# LDAQ-MOD-ENC4.net
KiCad netlist of a schematic drawn in EAGLE
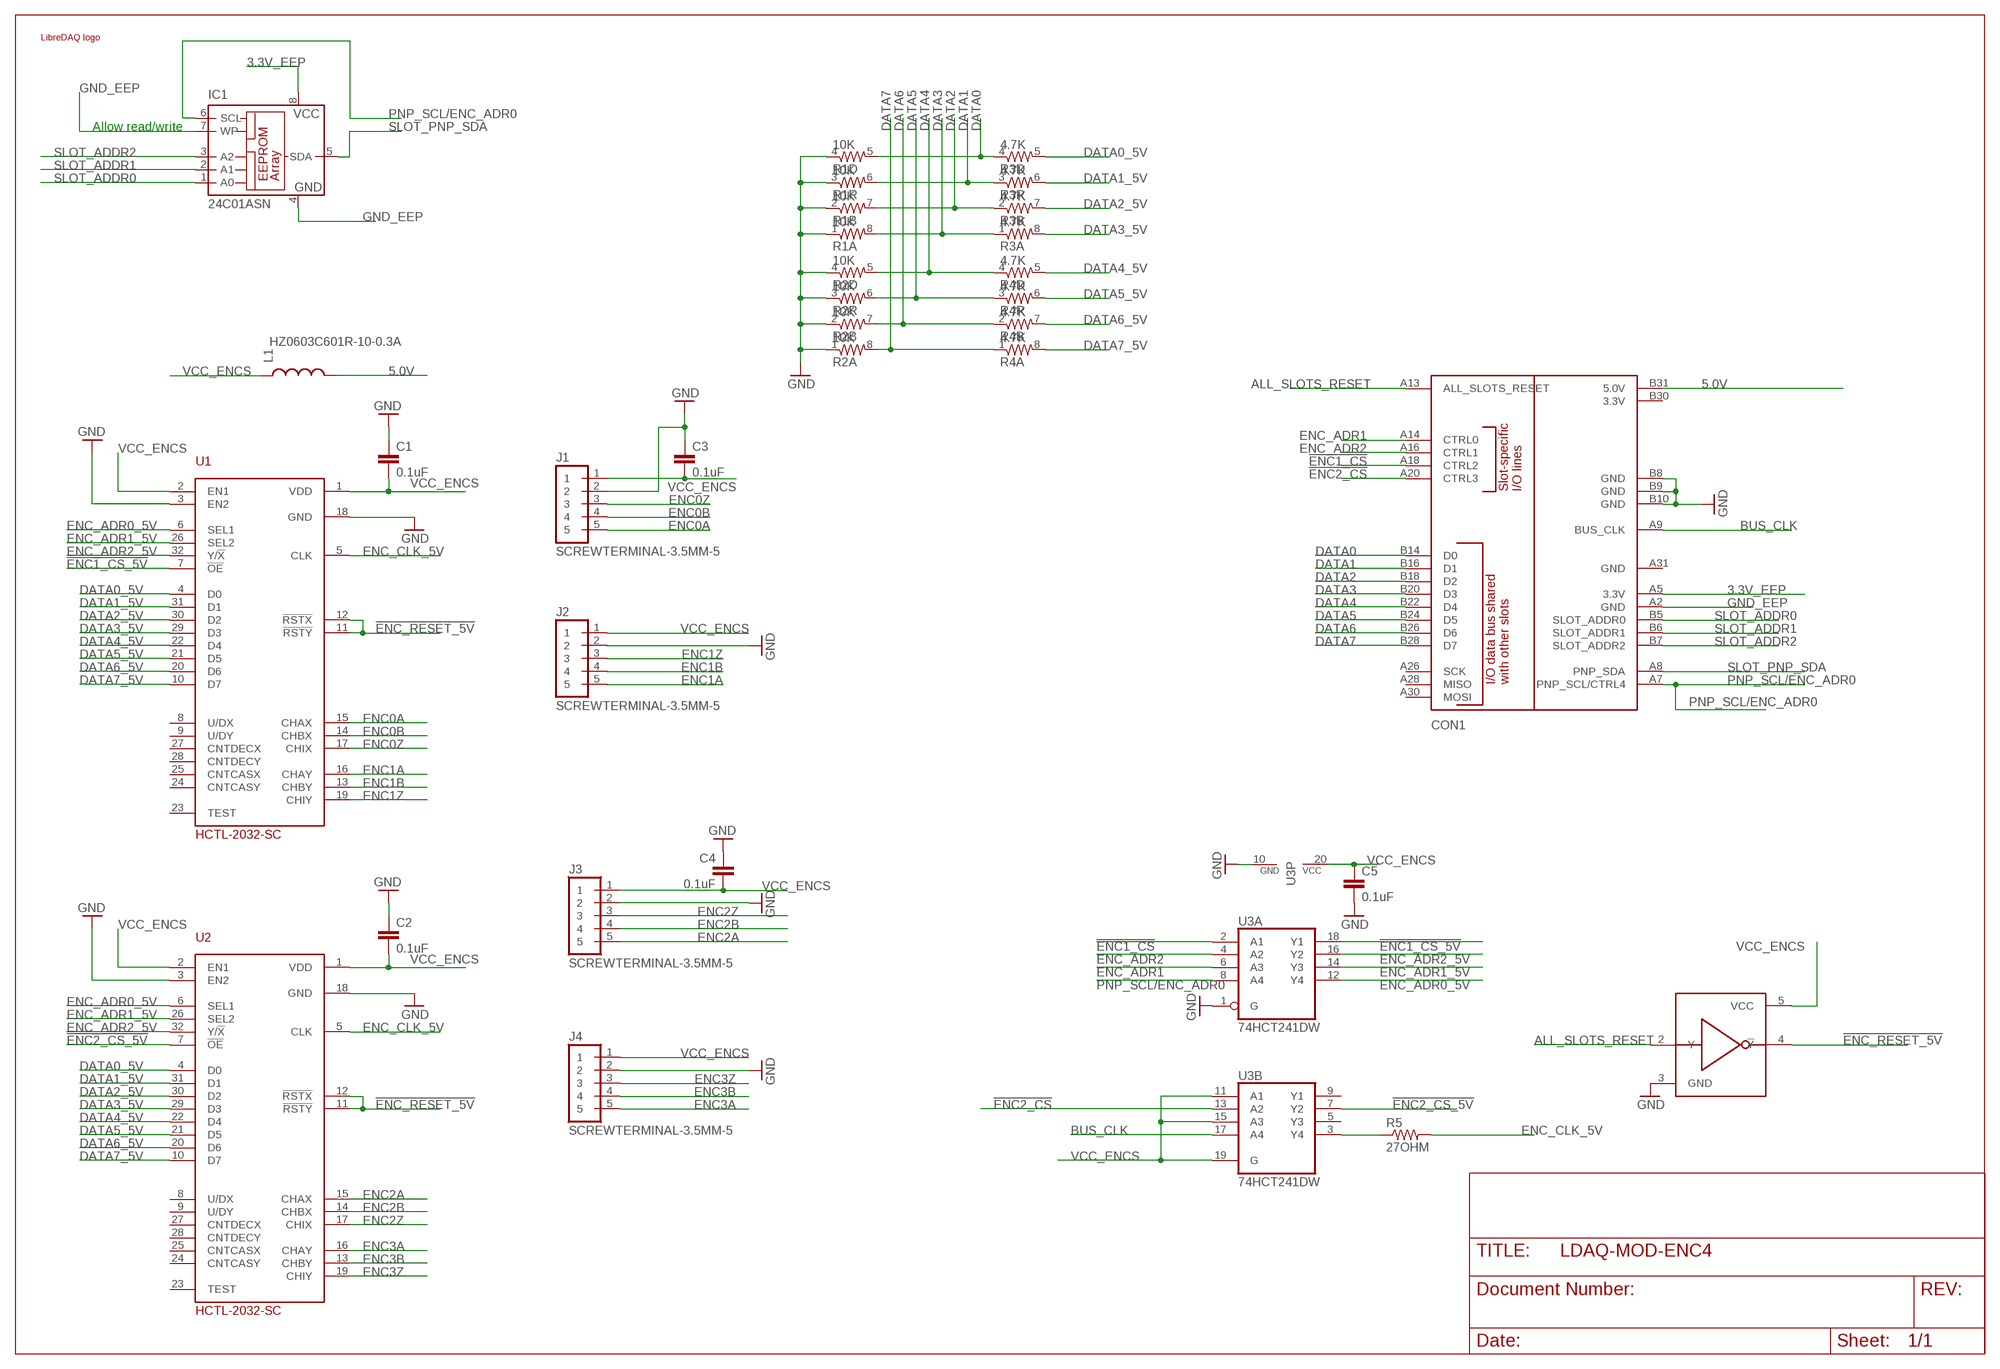
[diagram p0: schematic, sheet 1]

(export (version "E")
  (design (tool "Eeschema 10.0.6"))
  (components
    (comp (ref "C1")
      (value "0.1uF")
      (footprint "eagle-import:0603-CAP")
      (libsource (lib "eagle-import") (part "0.1UF-25V(+80/-20%)(0603)"))
    )
    (comp (ref "C2")
      (value "0.1uF")
      (footprint "eagle-import:0603-CAP")
      (libsource (lib "eagle-import") (part "0.1UF-25V(+80/-20%)(0603)"))
    )
    (comp (ref "C3")
      (value "0.1uF")
      (footprint "eagle-import:0603-CAP")
      (libsource (lib "eagle-import") (part "0.1UF-25V(+80/-20%)(0603)"))
    )
    (comp (ref "C4")
      (value "0.1uF")
      (footprint "eagle-import:0603-CAP")
      (libsource (lib "eagle-import") (part "0.1UF-25V(+80/-20%)(0603)"))
    )
    (comp (ref "C5")
      (value "0.1uF")
      (footprint "eagle-import:0603-CAP")
      (libsource (lib "eagle-import") (part "0.1UF-25V(+80/-20%)(0603)"))
    )
    (comp (ref "CON1")
      (value "BOARD")
      (footprint "eagle-import:PCI-E_64_EDGE_70X60_PADS-ONLY")
      (libsource (lib "eagle-import") (part "LIBREDAQ_DAUGHTER_BOARDPCI-64-SIZE1-PADS"))
    )
    (comp (ref "IC1")
      (value "24C01ASN")
      (footprint "eagle-import:SO-08")
      (fields (field (name "MPN") "AT24C01BN-SH-B"))
      (libsource (lib "eagle-import") (part "24CSN01A"))
    )
    (comp (ref "J1")
      (value "SCREWTERMINAL-3.5MM-5")
      (footprint "eagle-import:SCREWTERMINAL-3.5MM-5")
      (libsource (lib "eagle-import") (part "SCREWTERMINAL-3.5MM-5"))
    )
    (comp (ref "J2")
      (value "SCREWTERMINAL-3.5MM-5")
      (footprint "eagle-import:SCREWTERMINAL-3.5MM-5")
      (libsource (lib "eagle-import") (part "SCREWTERMINAL-3.5MM-5"))
    )
    (comp (ref "J3")
      (value "SCREWTERMINAL-3.5MM-5")
      (footprint "eagle-import:SCREWTERMINAL-3.5MM-5")
      (libsource (lib "eagle-import") (part "SCREWTERMINAL-3.5MM-5"))
    )
    (comp (ref "J4")
      (value "SCREWTERMINAL-3.5MM-5")
      (footprint "eagle-import:SCREWTERMINAL-3.5MM-5")
      (libsource (lib "eagle-import") (part "SCREWTERMINAL-3.5MM-5"))
    )
    (comp (ref "L1")
      (value "HZ0603C601R-10-0.3A")
      (footprint "eagle-import:0603")
      (libsource (lib "eagle-import") (part "INDUCTOR0603"))
    )
    (comp (ref "LOGO1")
      (value "LIBREDAQ_LOGO_MINILOGO_GENERIC")
      (footprint "eagle-import:LIBREDAQ_LOGO")
      (libsource (lib "eagle-import") (part "LIBREDAQ_LOGO_MINILOGO_GENERIC"))
    )
    (comp (ref "R1")
      (value "10K")
      (footprint "eagle-import:0603-ARV")
      (libsource (lib "eagle-import") (part "RESISTOR-ARRAY0603-ARV"))
    )
    (comp (ref "R2")
      (value "10K")
      (footprint "eagle-import:0603-ARV")
      (libsource (lib "eagle-import") (part "RESISTOR-ARRAY0603-ARV"))
    )
    (comp (ref "R3")
      (value "4.7K")
      (footprint "eagle-import:0603-ARV")
      (libsource (lib "eagle-import") (part "RESISTOR-ARRAY0603-ARV"))
    )
    (comp (ref "R4")
      (value "4.7K")
      (footprint "eagle-import:0603-ARV")
      (libsource (lib "eagle-import") (part "RESISTOR-ARRAY0603-ARV"))
    )
    (comp (ref "R5")
      (value "27OHM")
      (footprint "eagle-import:0603")
      (libsource (lib "eagle-import") (part "33OHM1/10W1%(0603)"))
    )
    (comp (ref "U1")
      (value "HCTL-2032-SC")
      (footprint "eagle-import:SOIC32")
      (libsource (lib "eagle-import") (part "HCTL-2032-SC"))
    )
    (comp (ref "U2")
      (value "HCTL-2032-SC")
      (footprint "eagle-import:SOIC32")
      (libsource (lib "eagle-import") (part "HCTL-2032-SC"))
    )
    (comp (ref "U3")
      (value "74HCT241DW")
      (footprint "eagle-import:SO20W")
      (libsource (lib "eagle-import") (part "74241DWHCT"))
    )
    (comp (ref "U4")
      (value "74AHCT1G04")
      (footprint "eagle-import:SOT353-SC70-5")
      (libsource (lib "eagle-import") (part "74AHCT1G04"))
    )
  )
  (nets
    (net (code "1") (name "/3.3V_EEP") (class "Default")
      (node (ref "CON1") (pin "A5") (pinfunction "3.3V_A5") (pintype "bidirectional"))
      (node (ref "IC1") (pin "8") (pinfunction "VCC_8") (pintype "power_in"))
    )
    (net (code "2") (name "/5.0V") (class "Default")
      (node (ref "CON1") (pin "B31") (pinfunction "5.0V_B31") (pintype "bidirectional"))
      (node (ref "L1") (pin "2") (pinfunction "2_2") (pintype "passive"))
    )
    (net (code "3") (name "/ALL_SLOTS_RESET") (class "Default")
      (node (ref "CON1") (pin "A13") (pinfunction "ALL_SLOTS_RESET_A13") (pintype "bidirectional"))
      (node (ref "U4") (pin "2") (pinfunction "Y_2") (pintype "bidirectional"))
    )
    (net (code "4") (name "/BUS_CLK") (class "Default")
      (node (ref "CON1") (pin "A9") (pinfunction "BUS_CLK_A9") (pintype "bidirectional"))
      (node (ref "U3") (pin "17") (pinfunction "A4_17") (pintype "input"))
    )
    (net (code "5") (name "/DATA0") (class "Default")
      (node (ref "CON1") (pin "B14") (pinfunction "D0_B14") (pintype "bidirectional"))
      (node (ref "R1") (pin "5") (pinfunction "2_5") (pintype "passive"))
      (node (ref "R3") (pin "4") (pinfunction "1_4") (pintype "passive"))
    )
    (net (code "6") (name "/DATA0_5V") (class "Default")
      (node (ref "R3") (pin "5") (pinfunction "2_5") (pintype "passive"))
      (node (ref "U1") (pin "4") (pinfunction "D0_4") (pintype "bidirectional"))
      (node (ref "U2") (pin "4") (pinfunction "D0_4") (pintype "bidirectional"))
    )
    (net (code "7") (name "/DATA1") (class "Default")
      (node (ref "CON1") (pin "B16") (pinfunction "D1_B16") (pintype "bidirectional"))
      (node (ref "R1") (pin "6") (pinfunction "2_6") (pintype "passive"))
      (node (ref "R3") (pin "3") (pinfunction "1_3") (pintype "passive"))
    )
    (net (code "8") (name "/DATA1_5V") (class "Default")
      (node (ref "R3") (pin "6") (pinfunction "2_6") (pintype "passive"))
      (node (ref "U1") (pin "31") (pinfunction "D1_31") (pintype "bidirectional"))
      (node (ref "U2") (pin "31") (pinfunction "D1_31") (pintype "bidirectional"))
    )
    (net (code "9") (name "/DATA2") (class "Default")
      (node (ref "CON1") (pin "B18") (pinfunction "D2_B18") (pintype "bidirectional"))
      (node (ref "R1") (pin "7") (pinfunction "2_7") (pintype "passive"))
      (node (ref "R3") (pin "2") (pinfunction "1_2") (pintype "passive"))
    )
    (net (code "10") (name "/DATA2_5V") (class "Default")
      (node (ref "R3") (pin "7") (pinfunction "2_7") (pintype "passive"))
      (node (ref "U1") (pin "30") (pinfunction "D2_30") (pintype "bidirectional"))
      (node (ref "U2") (pin "30") (pinfunction "D2_30") (pintype "bidirectional"))
    )
    (net (code "11") (name "/DATA3") (class "Default")
      (node (ref "CON1") (pin "B20") (pinfunction "D3_B20") (pintype "bidirectional"))
      (node (ref "R1") (pin "8") (pinfunction "2_8") (pintype "passive"))
      (node (ref "R3") (pin "1") (pinfunction "1_1") (pintype "passive"))
    )
    (net (code "12") (name "/DATA3_5V") (class "Default")
      (node (ref "R3") (pin "8") (pinfunction "2_8") (pintype "passive"))
      (node (ref "U1") (pin "29") (pinfunction "D3_29") (pintype "bidirectional"))
      (node (ref "U2") (pin "29") (pinfunction "D3_29") (pintype "bidirectional"))
    )
    (net (code "13") (name "/DATA4") (class "Default")
      (node (ref "CON1") (pin "B22") (pinfunction "D4_B22") (pintype "bidirectional"))
      (node (ref "R2") (pin "5") (pinfunction "2_5") (pintype "passive"))
      (node (ref "R4") (pin "4") (pinfunction "1_4") (pintype "passive"))
    )
    (net (code "14") (name "/DATA4_5V") (class "Default")
      (node (ref "R4") (pin "5") (pinfunction "2_5") (pintype "passive"))
      (node (ref "U1") (pin "22") (pinfunction "D4_22") (pintype "bidirectional"))
      (node (ref "U2") (pin "22") (pinfunction "D4_22") (pintype "bidirectional"))
    )
    (net (code "15") (name "/DATA5") (class "Default")
      (node (ref "CON1") (pin "B24") (pinfunction "D5_B24") (pintype "bidirectional"))
      (node (ref "R2") (pin "6") (pinfunction "2_6") (pintype "passive"))
      (node (ref "R4") (pin "3") (pinfunction "1_3") (pintype "passive"))
    )
    (net (code "16") (name "/DATA5_5V") (class "Default")
      (node (ref "R4") (pin "6") (pinfunction "2_6") (pintype "passive"))
      (node (ref "U1") (pin "21") (pinfunction "D5_21") (pintype "bidirectional"))
      (node (ref "U2") (pin "21") (pinfunction "D5_21") (pintype "bidirectional"))
    )
    (net (code "17") (name "/DATA6") (class "Default")
      (node (ref "CON1") (pin "B26") (pinfunction "D6_B26") (pintype "bidirectional"))
      (node (ref "R2") (pin "7") (pinfunction "2_7") (pintype "passive"))
      (node (ref "R4") (pin "2") (pinfunction "1_2") (pintype "passive"))
    )
    (net (code "18") (name "/DATA6_5V") (class "Default")
      (node (ref "R4") (pin "7") (pinfunction "2_7") (pintype "passive"))
      (node (ref "U1") (pin "20") (pinfunction "D6_20") (pintype "bidirectional"))
      (node (ref "U2") (pin "20") (pinfunction "D6_20") (pintype "bidirectional"))
    )
    (net (code "19") (name "/DATA7") (class "Default")
      (node (ref "CON1") (pin "B28") (pinfunction "D7_B28") (pintype "bidirectional"))
      (node (ref "R2") (pin "8") (pinfunction "2_8") (pintype "passive"))
      (node (ref "R4") (pin "1") (pinfunction "1_1") (pintype "passive"))
    )
    (net (code "20") (name "/DATA7_5V") (class "Default")
      (node (ref "R4") (pin "8") (pinfunction "2_8") (pintype "passive"))
      (node (ref "U1") (pin "10") (pinfunction "D7_10") (pintype "bidirectional"))
      (node (ref "U2") (pin "10") (pinfunction "D7_10") (pintype "bidirectional"))
    )
    (net (code "21") (name "/ENC0A") (class "Default")
      (node (ref "J1") (pin "5") (pinfunction "5_5") (pintype "bidirectional"))
      (node (ref "U1") (pin "15") (pinfunction "CHAX_15") (pintype "bidirectional"))
    )
    (net (code "22") (name "/ENC0B") (class "Default")
      (node (ref "J1") (pin "4") (pinfunction "4_4") (pintype "bidirectional"))
      (node (ref "U1") (pin "14") (pinfunction "CHBX_14") (pintype "bidirectional"))
    )
    (net (code "23") (name "/ENC0Z") (class "Default")
      (node (ref "J1") (pin "3") (pinfunction "3_3") (pintype "bidirectional"))
      (node (ref "U1") (pin "17") (pinfunction "CHIX_17") (pintype "bidirectional"))
    )
    (net (code "24") (name "/ENC1A") (class "Default")
      (node (ref "J2") (pin "5") (pinfunction "5_5") (pintype "bidirectional"))
      (node (ref "U1") (pin "16") (pinfunction "CHAY_16") (pintype "bidirectional"))
    )
    (net (code "25") (name "/ENC1B") (class "Default")
      (node (ref "J2") (pin "4") (pinfunction "4_4") (pintype "bidirectional"))
      (node (ref "U1") (pin "13") (pinfunction "CHBY_13") (pintype "bidirectional"))
    )
    (net (code "26") (name "/ENC1Z") (class "Default")
      (node (ref "J2") (pin "3") (pinfunction "3_3") (pintype "bidirectional"))
      (node (ref "U1") (pin "19") (pinfunction "CHIY_19") (pintype "bidirectional"))
    )
    (net (code "27") (name "/ENC2A") (class "Default")
      (node (ref "J3") (pin "5") (pinfunction "5_5") (pintype "bidirectional"))
      (node (ref "U2") (pin "15") (pinfunction "CHAX_15") (pintype "bidirectional"))
    )
    (net (code "28") (name "/ENC2B") (class "Default")
      (node (ref "J3") (pin "4") (pinfunction "4_4") (pintype "bidirectional"))
      (node (ref "U2") (pin "14") (pinfunction "CHBX_14") (pintype "bidirectional"))
    )
    (net (code "29") (name "/ENC2Z") (class "Default")
      (node (ref "J3") (pin "3") (pinfunction "3_3") (pintype "bidirectional"))
      (node (ref "U2") (pin "17") (pinfunction "CHIX_17") (pintype "bidirectional"))
    )
    (net (code "30") (name "/ENC3A") (class "Default")
      (node (ref "J4") (pin "5") (pinfunction "5_5") (pintype "bidirectional"))
      (node (ref "U2") (pin "16") (pinfunction "CHAY_16") (pintype "bidirectional"))
    )
    (net (code "31") (name "/ENC3B") (class "Default")
      (node (ref "J4") (pin "4") (pinfunction "4_4") (pintype "bidirectional"))
      (node (ref "U2") (pin "13") (pinfunction "CHBY_13") (pintype "bidirectional"))
    )
    (net (code "32") (name "/ENC3Z") (class "Default")
      (node (ref "J4") (pin "3") (pinfunction "3_3") (pintype "bidirectional"))
      (node (ref "U2") (pin "19") (pinfunction "CHIY_19") (pintype "bidirectional"))
    )
    (net (code "33") (name "/ENC_ADR0_5V") (class "Default")
      (node (ref "U1") (pin "6") (pinfunction "SEL1_6") (pintype "bidirectional"))
      (node (ref "U2") (pin "6") (pinfunction "SEL1_6") (pintype "bidirectional"))
      (node (ref "U3") (pin "12") (pinfunction "Y4_12") (pintype "tri_state"))
    )
    (net (code "34") (name "/ENC_ADR1") (class "Default")
      (node (ref "CON1") (pin "A14") (pinfunction "CTRL0_A14") (pintype "bidirectional"))
      (node (ref "U3") (pin "6") (pinfunction "A3_6") (pintype "input"))
    )
    (net (code "35") (name "/ENC_ADR1_5V") (class "Default")
      (node (ref "U1") (pin "26") (pinfunction "SEL2_26") (pintype "bidirectional"))
      (node (ref "U2") (pin "26") (pinfunction "SEL2_26") (pintype "bidirectional"))
      (node (ref "U3") (pin "14") (pinfunction "Y3_14") (pintype "tri_state"))
    )
    (net (code "36") (name "/ENC_ADR2") (class "Default")
      (node (ref "CON1") (pin "A16") (pinfunction "CTRL1_A16") (pintype "bidirectional"))
      (node (ref "U3") (pin "4") (pinfunction "A2_4") (pintype "input"))
    )
    (net (code "37") (name "/ENC_ADR2_5V") (class "Default")
      (node (ref "U1") (pin "32") (pinfunction "Y/~{X}_32") (pintype "bidirectional"))
      (node (ref "U2") (pin "32") (pinfunction "Y/~{X}_32") (pintype "bidirectional"))
      (node (ref "U3") (pin "16") (pinfunction "Y2_16") (pintype "tri_state"))
    )
    (net (code "38") (name "/ENC_CLK_5V") (class "Default")
      (node (ref "R5") (pin "2") (pinfunction "2_2") (pintype "passive"))
      (node (ref "U1") (pin "5") (pinfunction "CLK_5") (pintype "bidirectional"))
      (node (ref "U2") (pin "5") (pinfunction "CLK_5") (pintype "bidirectional"))
    )
    (net (code "39") (name "/GND_EEP") (class "Default")
      (node (ref "CON1") (pin "A2") (pinfunction "GND_A2") (pintype "bidirectional"))
      (node (ref "IC1") (pin "4") (pinfunction "GND_4") (pintype "power_in"))
      (node (ref "IC1") (pin "7") (pinfunction "WP_7") (pintype "input"))
    )
    (net (code "40") (name "/PNP_SCL{slash}ENC_ADR0") (class "Default")
      (node (ref "CON1") (pin "A7") (pinfunction "PNP_SCL/CTRL4_A7") (pintype "bidirectional"))
      (node (ref "IC1") (pin "6") (pinfunction "SCL_6") (pintype "input"))
      (node (ref "U3") (pin "8") (pinfunction "A4_8") (pintype "input"))
    )
    (net (code "41") (name "/SLOT_ADDR0") (class "Default")
      (node (ref "CON1") (pin "B5") (pinfunction "SLOT_ADDR0_B5") (pintype "bidirectional"))
      (node (ref "IC1") (pin "1") (pinfunction "A0_1") (pintype "input"))
    )
    (net (code "42") (name "/SLOT_ADDR1") (class "Default")
      (node (ref "CON1") (pin "B6") (pinfunction "SLOT_ADDR1_B6") (pintype "bidirectional"))
      (node (ref "IC1") (pin "2") (pinfunction "A1_2") (pintype "input"))
    )
    (net (code "43") (name "/SLOT_ADDR2") (class "Default")
      (node (ref "CON1") (pin "B7") (pinfunction "SLOT_ADDR2_B7") (pintype "bidirectional"))
      (node (ref "IC1") (pin "3") (pinfunction "A2_3") (pintype "input"))
    )
    (net (code "44") (name "/SLOT_PNP_SDA") (class "Default")
      (node (ref "CON1") (pin "A8") (pinfunction "PNP_SDA_A8") (pintype "bidirectional"))
      (node (ref "IC1") (pin "5") (pinfunction "SDA_5") (pintype "bidirectional"))
    )
    (net (code "45") (name "/VCC_ENCS") (class "Default")
      (node (ref "C1") (pin "2") (pinfunction "2_2") (pintype "passive"))
      (node (ref "C2") (pin "2") (pinfunction "2_2") (pintype "passive"))
      (node (ref "C3") (pin "2") (pinfunction "2_2") (pintype "passive"))
      (node (ref "C4") (pin "2") (pinfunction "2_2") (pintype "passive"))
      (node (ref "C5") (pin "1") (pinfunction "1_1") (pintype "passive"))
      (node (ref "J1") (pin "1") (pinfunction "1_1") (pintype "bidirectional"))
      (node (ref "J2") (pin "1") (pinfunction "1_1") (pintype "bidirectional"))
      (node (ref "J3") (pin "1") (pinfunction "1_1") (pintype "bidirectional"))
      (node (ref "J4") (pin "1") (pinfunction "1_1") (pintype "bidirectional"))
      (node (ref "L1") (pin "1") (pinfunction "1_1") (pintype "passive"))
      (node (ref "U1") (pin "1") (pinfunction "VDD_1") (pintype "bidirectional"))
      (node (ref "U1") (pin "2") (pinfunction "EN1_2") (pintype "bidirectional"))
      (node (ref "U2") (pin "1") (pinfunction "VDD_1") (pintype "bidirectional"))
      (node (ref "U2") (pin "2") (pinfunction "EN1_2") (pintype "bidirectional"))
      (node (ref "U3") (pin "11") (pinfunction "A1_11") (pintype "input"))
      (node (ref "U3") (pin "15") (pinfunction "A3_15") (pintype "input"))
      (node (ref "U3") (pin "19") (pinfunction "G_19") (pintype "input"))
      (node (ref "U3") (pin "20") (pinfunction "VCC_20") (pintype "power_in"))
      (node (ref "U4") (pin "5") (pinfunction "VCC_5") (pintype "bidirectional"))
    )
    (net (code "46") (name "/~{ENC1_CS_5V}") (class "Default")
      (node (ref "U1") (pin "7") (pinfunction "~{OE}_7") (pintype "bidirectional"))
      (node (ref "U3") (pin "18") (pinfunction "Y1_18") (pintype "tri_state"))
    )
    (net (code "47") (name "/~{ENC1_CS}") (class "Default")
      (node (ref "CON1") (pin "A18") (pinfunction "CTRL2_A18") (pintype "bidirectional"))
      (node (ref "U3") (pin "2") (pinfunction "A1_2") (pintype "input"))
    )
    (net (code "48") (name "/~{ENC2_CS_5V}") (class "Default")
      (node (ref "U2") (pin "7") (pinfunction "~{OE}_7") (pintype "bidirectional"))
      (node (ref "U3") (pin "7") (pinfunction "Y2_7") (pintype "tri_state"))
    )
    (net (code "49") (name "/~{ENC2_CS}") (class "Default")
      (node (ref "CON1") (pin "A20") (pinfunction "CTRL3_A20") (pintype "bidirectional"))
      (node (ref "U3") (pin "13") (pinfunction "A2_13") (pintype "input"))
    )
    (net (code "50") (name "/~{ENC_RESET_5V}") (class "Default")
      (node (ref "U1") (pin "11") (pinfunction "~{RSTY}_11") (pintype "bidirectional"))
      (node (ref "U1") (pin "12") (pinfunction "~{RSTX}_12") (pintype "bidirectional"))
      (node (ref "U2") (pin "11") (pinfunction "~{RSTY}_11") (pintype "bidirectional"))
      (node (ref "U2") (pin "12") (pinfunction "~{RSTX}_12") (pintype "bidirectional"))
      (node (ref "U4") (pin "4") (pinfunction "~{Y}_4") (pintype "bidirectional"))
    )
    (net (code "51") (name "GND") (class "Default")
      (node (ref "C1") (pin "1") (pinfunction "1_1") (pintype "passive"))
      (node (ref "C2") (pin "1") (pinfunction "1_1") (pintype "passive"))
      (node (ref "C3") (pin "1") (pinfunction "1_1") (pintype "passive"))
      (node (ref "C4") (pin "1") (pinfunction "1_1") (pintype "passive"))
      (node (ref "C5") (pin "2") (pinfunction "2_2") (pintype "passive"))
      (node (ref "CON1") (pin "B10") (pinfunction "GND_B10") (pintype "bidirectional"))
      (node (ref "CON1") (pin "B8") (pinfunction "GND_B8") (pintype "bidirectional"))
      (node (ref "CON1") (pin "B9") (pinfunction "GND_B9") (pintype "bidirectional"))
      (node (ref "J1") (pin "2") (pinfunction "2_2") (pintype "bidirectional"))
      (node (ref "J2") (pin "2") (pinfunction "2_2") (pintype "bidirectional"))
      (node (ref "J3") (pin "2") (pinfunction "2_2") (pintype "bidirectional"))
      (node (ref "J4") (pin "2") (pinfunction "2_2") (pintype "bidirectional"))
      (node (ref "R1") (pin "1") (pinfunction "1_1") (pintype "passive"))
      (node (ref "R1") (pin "2") (pinfunction "1_2") (pintype "passive"))
      (node (ref "R1") (pin "3") (pinfunction "1_3") (pintype "passive"))
      (node (ref "R1") (pin "4") (pinfunction "1_4") (pintype "passive"))
      (node (ref "R2") (pin "1") (pinfunction "1_1") (pintype "passive"))
      (node (ref "R2") (pin "2") (pinfunction "1_2") (pintype "passive"))
      (node (ref "R2") (pin "3") (pinfunction "1_3") (pintype "passive"))
      (node (ref "R2") (pin "4") (pinfunction "1_4") (pintype "passive"))
      (node (ref "U1") (pin "18") (pinfunction "GND_18") (pintype "bidirectional"))
      (node (ref "U1") (pin "3") (pinfunction "EN2_3") (pintype "bidirectional"))
      (node (ref "U2") (pin "18") (pinfunction "GND_18") (pintype "bidirectional"))
      (node (ref "U2") (pin "3") (pinfunction "EN2_3") (pintype "bidirectional"))
      (node (ref "U3") (pin "1") (pinfunction "G_1") (pintype "input"))
      (node (ref "U3") (pin "10") (pinfunction "GND_10") (pintype "power_in"))
      (node (ref "U4") (pin "3") (pinfunction "GND_3") (pintype "bidirectional"))
    )
    (net (code "52") (name "Net-(U3B-Y4)") (class "Default")
      (node (ref "R5") (pin "1") (pinfunction "1_1") (pintype "passive"))
      (node (ref "U3") (pin "3") (pinfunction "Y4_3") (pintype "tri_state"))
    )
    (net (code "53") (name "unconnected-(CON1-3.3V-PadB30)") (class "Default")
      (node (ref "CON1") (pin "B30") (pinfunction "3.3V_B30") (pintype "bidirectional"))
    )
    (net (code "54") (name "unconnected-(CON1-GND-PadA31)") (class "Default")
      (node (ref "CON1") (pin "A31") (pinfunction "GND_A31") (pintype "bidirectional"))
    )
    (net (code "55") (name "unconnected-(CON1-MISO-PadA28)") (class "Default")
      (node (ref "CON1") (pin "A28") (pinfunction "MISO_A28") (pintype "bidirectional"))
    )
    (net (code "56") (name "unconnected-(CON1-MOSI-PadA30)") (class "Default")
      (node (ref "CON1") (pin "A30") (pinfunction "MOSI_A30") (pintype "bidirectional"))
    )
    (net (code "57") (name "unconnected-(CON1-SCK-PadA26)") (class "Default")
      (node (ref "CON1") (pin "A26") (pinfunction "SCK_A26") (pintype "bidirectional"))
    )
    (net (code "58") (name "unconnected-(U1-CNTCASX-Pad25)") (class "Default")
      (node (ref "U1") (pin "25") (pinfunction "CNTCASX_25") (pintype "bidirectional"))
    )
    (net (code "59") (name "unconnected-(U1-CNTCASY-Pad24)") (class "Default")
      (node (ref "U1") (pin "24") (pinfunction "CNTCASY_24") (pintype "bidirectional"))
    )
    (net (code "60") (name "unconnected-(U1-CNTDECX-Pad27)") (class "Default")
      (node (ref "U1") (pin "27") (pinfunction "CNTDECX_27") (pintype "bidirectional"))
    )
    (net (code "61") (name "unconnected-(U1-CNTDECY-Pad28)") (class "Default")
      (node (ref "U1") (pin "28") (pinfunction "CNTDECY_28") (pintype "bidirectional"))
    )
    (net (code "62") (name "unconnected-(U1-TEST-Pad23)") (class "Default")
      (node (ref "U1") (pin "23") (pinfunction "TEST_23") (pintype "bidirectional"))
    )
    (net (code "63") (name "unconnected-(U1-U{slash}DX-Pad8)") (class "Default")
      (node (ref "U1") (pin "8") (pinfunction "U/DX_8") (pintype "bidirectional"))
    )
    (net (code "64") (name "unconnected-(U1-U{slash}DY-Pad9)") (class "Default")
      (node (ref "U1") (pin "9") (pinfunction "U/DY_9") (pintype "bidirectional"))
    )
    (net (code "65") (name "unconnected-(U2-CNTCASX-Pad25)") (class "Default")
      (node (ref "U2") (pin "25") (pinfunction "CNTCASX_25") (pintype "bidirectional"))
    )
    (net (code "66") (name "unconnected-(U2-CNTCASY-Pad24)") (class "Default")
      (node (ref "U2") (pin "24") (pinfunction "CNTCASY_24") (pintype "bidirectional"))
    )
    (net (code "67") (name "unconnected-(U2-CNTDECX-Pad27)") (class "Default")
      (node (ref "U2") (pin "27") (pinfunction "CNTDECX_27") (pintype "bidirectional"))
    )
    (net (code "68") (name "unconnected-(U2-CNTDECY-Pad28)") (class "Default")
      (node (ref "U2") (pin "28") (pinfunction "CNTDECY_28") (pintype "bidirectional"))
    )
    (net (code "69") (name "unconnected-(U2-TEST-Pad23)") (class "Default")
      (node (ref "U2") (pin "23") (pinfunction "TEST_23") (pintype "bidirectional"))
    )
    (net (code "70") (name "unconnected-(U2-U{slash}DX-Pad8)") (class "Default")
      (node (ref "U2") (pin "8") (pinfunction "U/DX_8") (pintype "bidirectional"))
    )
    (net (code "71") (name "unconnected-(U2-U{slash}DY-Pad9)") (class "Default")
      (node (ref "U2") (pin "9") (pinfunction "U/DY_9") (pintype "bidirectional"))
    )
    (net (code "72") (name "unconnected-(U3B-Y1-Pad9)") (class "Default")
      (node (ref "U3") (pin "9") (pinfunction "Y1_9") (pintype "tri_state"))
    )
    (net (code "73") (name "unconnected-(U3B-Y3-Pad5)") (class "Default")
      (node (ref "U3") (pin "5") (pinfunction "Y3_5") (pintype "tri_state"))
    )
  )
)
